# Reaccion.net
KiCad netlist of a schematic drawn in EAGLE
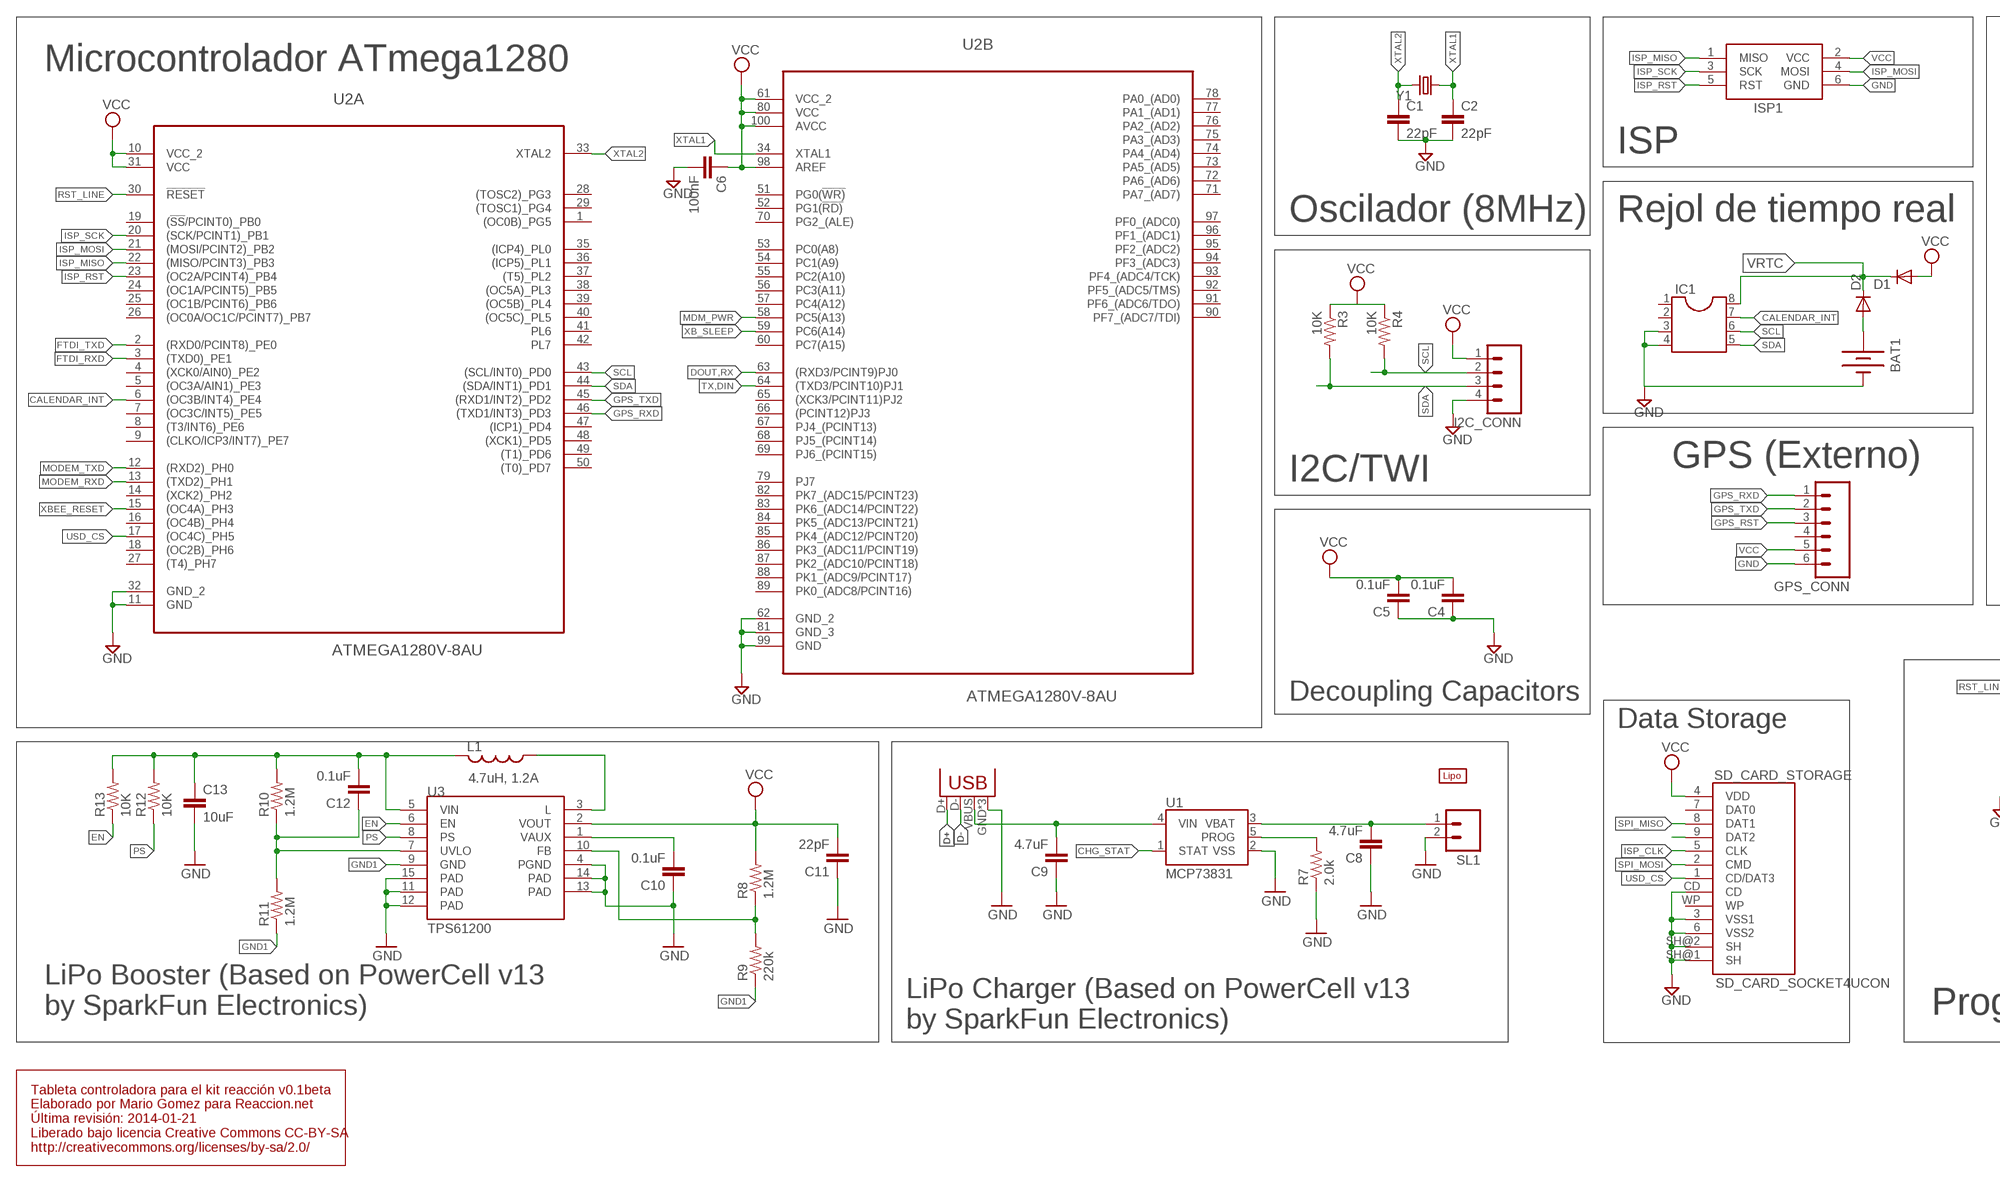
[diagram p0: schematic, sheet 1, part 1 of 2]
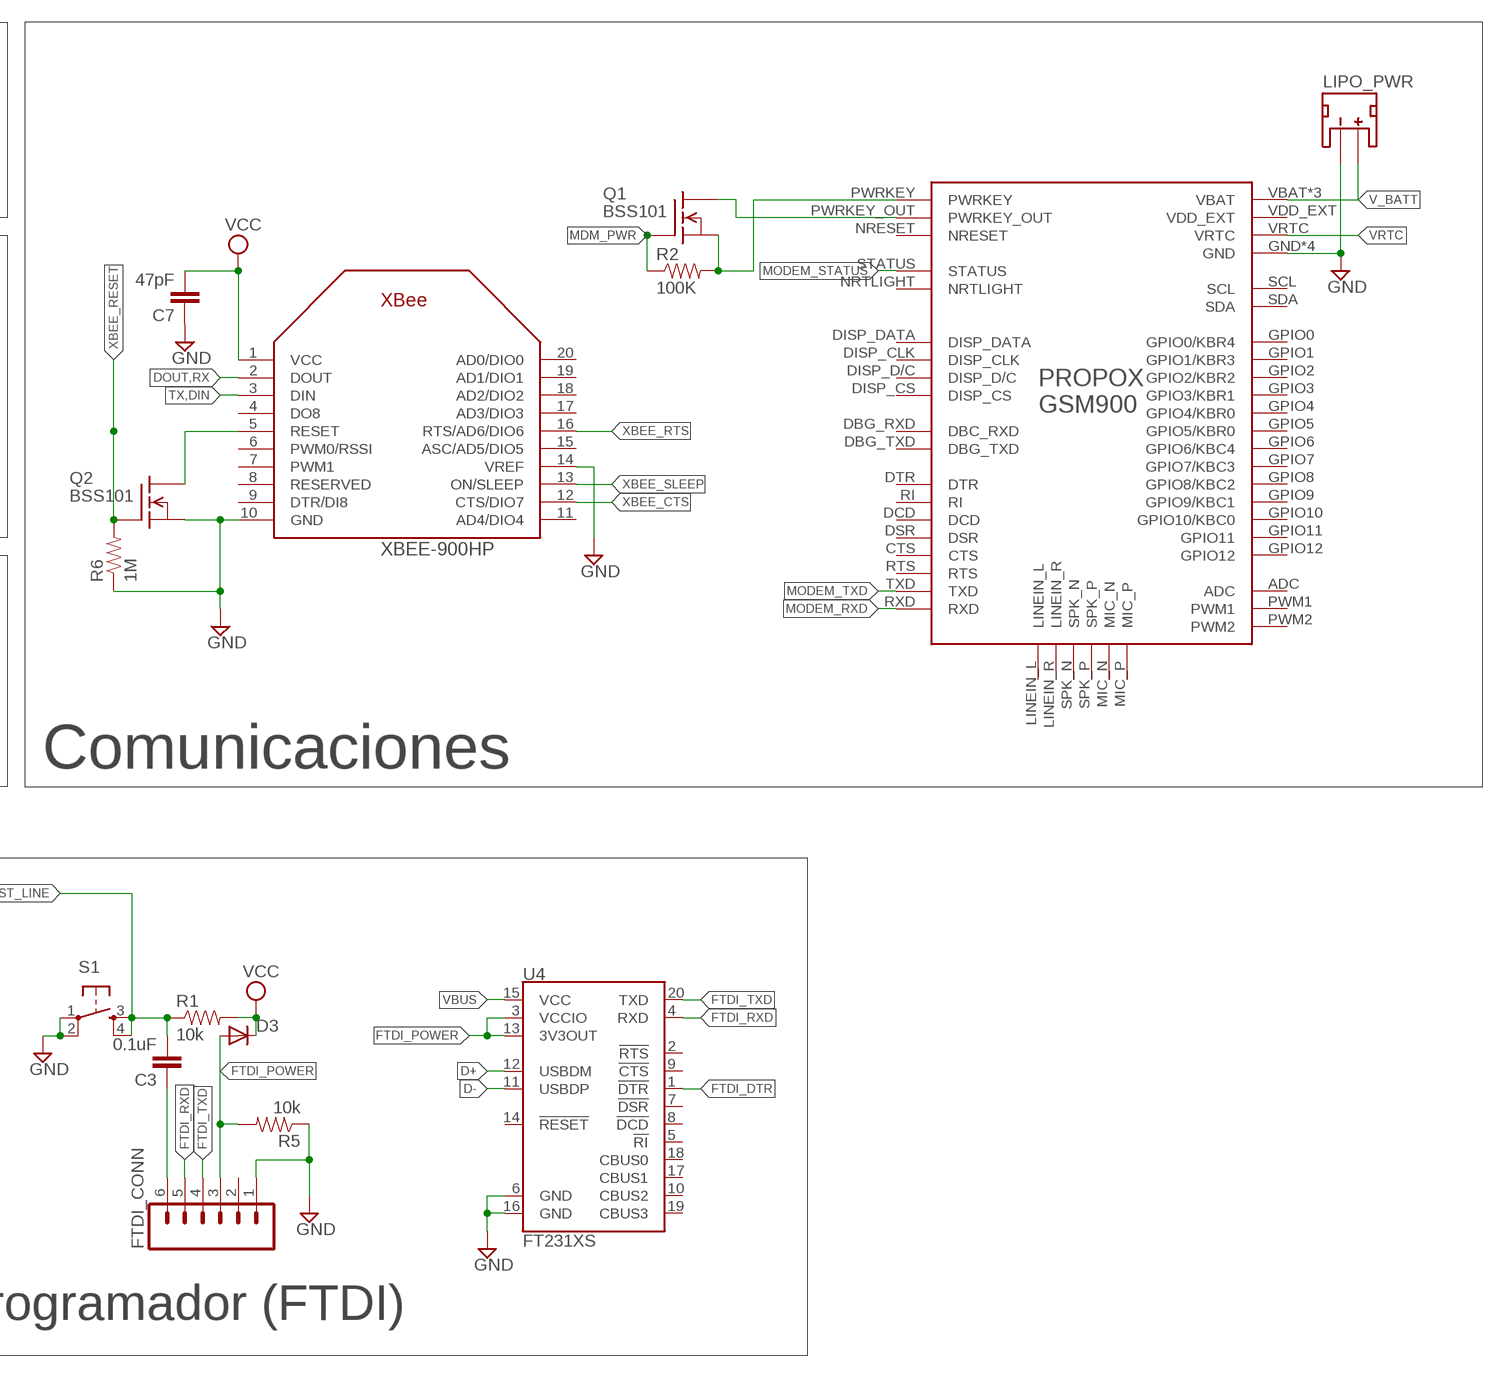
[diagram p1: schematic, sheet 1, part 2 of 2]

(export (version "E")
  (design (tool "Eeschema 10.0.6"))
  (components
    (comp (ref "BAT1")
      (value "BATTERY12PTH")
      (footprint "eagle-import:BATTCON_12MM_PTH")
      (libsource (lib "eagle-import") (part "BATTERY12PTH"))
    )
    (comp (ref "C1")
      (value "22pF")
      (footprint "eagle-import:0805")
      (libsource (lib "eagle-import") (part "CAP0805"))
    )
    (comp (ref "C2")
      (value "22pF")
      (footprint "eagle-import:0805")
      (libsource (lib "eagle-import") (part "CAP0805"))
    )
    (comp (ref "C3")
      (value "0.1uF")
      (footprint "eagle-import:0805")
      (libsource (lib "eagle-import") (part "CAP0805"))
    )
    (comp (ref "C4")
      (value "0.1uF")
      (footprint "eagle-import:0805")
      (libsource (lib "eagle-import") (part "1.0UF-25V-+80/-20(0805)"))
    )
    (comp (ref "C5")
      (value "0.1uF")
      (footprint "eagle-import:0805")
      (libsource (lib "eagle-import") (part "CAP0805"))
    )
    (comp (ref "C6")
      (value "100nF")
      (footprint "eagle-import:0805")
      (libsource (lib "eagle-import") (part "CAP0805"))
    )
    (comp (ref "C7")
      (value "47pF")
      (footprint "eagle-import:0805")
      (libsource (lib "eagle-import") (part "1.0UF-25V-+80/-20(0805)"))
    )
    (comp (ref "C8")
      (value "4.7uF")
      (footprint "eagle-import:0603-CAP")
      (libsource (lib "eagle-import") (part "4.7UF-6.3V-10%(0603)0603"))
    )
    (comp (ref "C9")
      (value "4.7uF")
      (footprint "eagle-import:0603-CAP")
      (libsource (lib "eagle-import") (part "4.7UF-6.3V-10%(0603)0603"))
    )
    (comp (ref "C10")
      (value "0.1uF")
      (footprint "eagle-import:0805")
      (libsource (lib "eagle-import") (part "1.0UF-25V-+80/-20(0805)"))
    )
    (comp (ref "C11")
      (value "22pF")
      (footprint "eagle-import:0805")
      (libsource (lib "eagle-import") (part "1.0UF-25V-+80/-20(0805)"))
    )
    (comp (ref "C12")
      (value "0.1uF")
      (footprint "eagle-import:0805")
      (libsource (lib "eagle-import") (part "1.0UF-25V-+80/-20(0805)"))
    )
    (comp (ref "C13")
      (value "10uF")
      (footprint "eagle-import:1206")
      (libsource (lib "eagle-import") (part "2.2UF-CERCAP-10009"))
    )
    (comp (ref "D1")
      (value "DIODESOD")
      (footprint "eagle-import:SOD-323")
      (libsource (lib "eagle-import") (part "DIODESOD"))
    )
    (comp (ref "D2")
      (value "DIODESOD")
      (footprint "eagle-import:SOD-323")
      (libsource (lib "eagle-import") (part "DIODESOD"))
    )
    (comp (ref "D3")
      (value "DIODESOD")
      (footprint "eagle-import:SOD-323")
      (libsource (lib "eagle-import") (part "DIODESOD"))
    )
    (comp (ref "FTDI_CONN")
      (value "M06SIP")
      (footprint "eagle-import:1X06")
      (libsource (lib "eagle-import") (part "M06SIP"))
    )
    (comp (ref "GPS_CONN")
      (value "M06SIP")
      (footprint "eagle-import:1X06")
      (libsource (lib "eagle-import") (part "M06SIP"))
    )
    (comp (ref "GSM_MODEM")
      (value "PROPOXGSM900")
      (footprint "eagle-import:CONN-13X2")
      (libsource (lib "eagle-import") (part "PROPOXGSM900"))
    )
    (comp (ref "I2C_CONN")
      (value "M04PTH")
      (footprint "eagle-import:1X04")
      (libsource (lib "eagle-import") (part "M04PTH"))
    )
    (comp (ref "IC1")
      (value "DIL8")
      (footprint "eagle-import:DIL08")
      (libsource (lib "eagle-import") (part "DIL8"))
    )
    (comp (ref "ISP1")
      (value "AVRISP-6")
      (footprint "eagle-import:AVRISP")
      (libsource (lib "eagle-import") (part "AVRISP-6"))
    )
    (comp (ref "JP1")
      (value "USB-MICROB")
      (footprint "eagle-import:USB-MICROB")
      (libsource (lib "eagle-import") (part "USB-MICROB"))
    )
    (comp (ref "L1")
      (value "4.7uH, 1.2A")
      (footprint "eagle-import:CDRH2D09")
      (libsource (lib "eagle-import") (part "INDUCTOR."))
    )
    (comp (ref "LIPO_PWR")
      (value "JST_2MM_MALE")
      (footprint "eagle-import:JST-2-SMD")
      (libsource (lib "eagle-import") (part "JST_2MM_MALE"))
    )
    (comp (ref "Q1")
      (value "BSS101")
      (footprint "eagle-import:TO92")
      (libsource (lib "eagle-import") (part "BSS101"))
    )
    (comp (ref "Q2")
      (value "BSS101")
      (footprint "eagle-import:TO92")
      (libsource (lib "eagle-import") (part "BSS101"))
    )
    (comp (ref "R1")
      (value "10k")
      (footprint "eagle-import:0805")
      (libsource (lib "eagle-import") (part "RESISTOR0805-RES"))
    )
    (comp (ref "R2")
      (value "100K")
      (footprint "eagle-import:0805")
      (libsource (lib "eagle-import") (part "RESISTOR0805-RES"))
    )
    (comp (ref "R3")
      (value "10K")
      (footprint "eagle-import:0805")
      (libsource (lib "eagle-import") (part "RESISTOR0805-RES"))
    )
    (comp (ref "R4")
      (value "10K")
      (footprint "eagle-import:0805")
      (libsource (lib "eagle-import") (part "RESISTOR0805-RES"))
    )
    (comp (ref "R5")
      (value "10k")
      (footprint "eagle-import:0805")
      (libsource (lib "eagle-import") (part "RESISTOR0805-RES"))
    )
    (comp (ref "R6")
      (value "1M")
      (footprint "eagle-import:0805")
      (libsource (lib "eagle-import") (part "RESISTOR0805-RES"))
    )
    (comp (ref "R7")
      (value "2.0k")
      (footprint "eagle-import:0603-RES")
      (libsource (lib "eagle-import") (part "2.0KOHM1/10W5%(0603)"))
    )
    (comp (ref "R8")
      (value "1.2M")
      (footprint "eagle-import:0603-RES")
      (libsource (lib "eagle-import") (part "2.0KOHM1/10W5%(0603)"))
    )
    (comp (ref "R9")
      (value "220k")
      (footprint "eagle-import:0603-RES")
      (libsource (lib "eagle-import") (part "2.0KOHM1/10W5%(0603)"))
    )
    (comp (ref "R10")
      (value "1.2M")
      (footprint "eagle-import:0603-RES")
      (libsource (lib "eagle-import") (part "2.0KOHM1/10W5%(0603)"))
    )
    (comp (ref "R11")
      (value "1.2M")
      (footprint "eagle-import:0603-RES")
      (libsource (lib "eagle-import") (part "2.0KOHM1/10W5%(0603)"))
    )
    (comp (ref "R12")
      (value "10K")
      (footprint "eagle-import:0603-RES")
      (libsource (lib "eagle-import") (part "2.0KOHM1/10W5%(0603)"))
    )
    (comp (ref "R13")
      (value "10K")
      (footprint "eagle-import:0603-RES")
      (libsource (lib "eagle-import") (part "2.0KOHM1/10W5%(0603)"))
    )
    (comp (ref "S1")
      (value "TAC_SWITCHPTH")
      (footprint "eagle-import:TACTILE-PTH")
      (libsource (lib "eagle-import") (part "TAC_SWITCHPTH"))
    )
    (comp (ref "SD_CARD_STORAGE")
      (value "SD_CARD_SOCKET4UCON")
      (footprint "eagle-import:SDCARD_4UCONN")
      (libsource (lib "eagle-import") (part "SD_CARD_SOCKET4UCON"))
    )
    (comp (ref "SL1")
      (value "M02")
      (footprint "eagle-import:02P")
      (libsource (lib "eagle-import") (part "M02"))
    )
    (comp (ref "U$2")
      (value "LIPO-OUTLINE2000")
      (footprint "eagle-import:LIPO-2000")
      (libsource (lib "eagle-import") (part "LIPO-OUTLINE2000"))
    )
    (comp (ref "U1")
      (value "MCP73831")
      (footprint "eagle-import:SOT23-5")
      (libsource (lib "eagle-import") (part "MCP73831"))
    )
    (comp (ref "U2")
      (value "ATMEGA1280V-8AU")
      (footprint "eagle-import:QFP50P1600X1600X120-100N")
      (libsource (lib "eagle-import") (part "ATMEGA1280V-8AU"))
    )
    (comp (ref "U3")
      (value "TPS61200")
      (footprint "eagle-import:QFN-10_PAD")
      (libsource (lib "eagle-import") (part "TPS61200"))
    )
    (comp (ref "U4")
      (value "FT231XS")
      (footprint "eagle-import:SSOP20_L")
      (libsource (lib "eagle-import") (part "FT231XS"))
    )
    (comp (ref "XBEE-900HP")
      (value "XBEE")
      (footprint "eagle-import:XBEE")
      (libsource (lib "eagle-import") (part "XBEE"))
    )
    (comp (ref "Y1")
      (value "CRYSTAL10.5X4.8")
      (footprint "eagle-import:CRYSTAL-SMD-10.5X4.8-2PIN")
      (libsource (lib "eagle-import") (part "CRYSTAL10.5X4.8"))
    )
  )
  (nets
    (net (code "1") (name "CALENDAR_INT") (class "Default")
      (node (ref "IC1") (pin "7") (pinfunction "7_7") (pintype "passive"))
      (node (ref "U2") (pin "6") (pinfunction "(OC3B/INT4)_PE4_6") (pintype "bidirectional"))
    )
    (net (code "2") (name "CHG_STAT") (class "Default")
      (node (ref "U1") (pin "1") (pinfunction "STAT_1") (pintype "output"))
    )
    (net (code "3") (name "D+") (class "Default")
      (node (ref "JP1") (pin "D+") (pinfunction "D+_D+") (pintype "bidirectional"))
      (node (ref "U4") (pin "12") (pinfunction "USBDM_12") (pintype "bidirectional"))
    )
    (net (code "4") (name "D-") (class "Default")
      (node (ref "JP1") (pin "D-") (pinfunction "D-_D-") (pintype "bidirectional"))
      (node (ref "U4") (pin "11") (pinfunction "USBDP_11") (pintype "bidirectional"))
    )
    (net (code "5") (name "DOUT,RX") (class "Default")
      (node (ref "U2") (pin "63") (pinfunction "(RXD3/PCINT9)PJ0_63") (pintype "bidirectional"))
      (node (ref "XBEE-900HP") (pin "2") (pinfunction "DOUT_2") (pintype "output"))
    )
    (net (code "6") (name "EN") (class "Default")
      (node (ref "R13") (pin "1") (pinfunction "1_1") (pintype "passive"))
      (node (ref "U3") (pin "6") (pinfunction "EN_6") (pintype "input"))
    )
    (net (code "7") (name "FTDI_DTR") (class "Default")
      (node (ref "C3") (pin "1") (pinfunction "1_1") (pintype "passive"))
      (node (ref "FTDI_CONN") (pin "6") (pinfunction "6_6") (pintype "passive"))
      (node (ref "U4") (pin "1") (pinfunction "~{DTR}_1") (pintype "bidirectional"))
    )
    (net (code "8") (name "FTDI_POWER") (class "Default")
      (node (ref "D3") (pin "2") (pinfunction "A_2") (pintype "passive"))
      (node (ref "FTDI_CONN") (pin "3") (pinfunction "3_3") (pintype "passive"))
      (node (ref "R5") (pin "2") (pinfunction "2_2") (pintype "passive"))
      (node (ref "U4") (pin "13") (pinfunction "3V3OUT_13") (pintype "bidirectional"))
      (node (ref "U4") (pin "3") (pinfunction "VCCIO_3") (pintype "bidirectional"))
    )
    (net (code "9") (name "FTDI_RXD") (class "Default")
      (node (ref "FTDI_CONN") (pin "5") (pinfunction "5_5") (pintype "passive"))
      (node (ref "U2") (pin "3") (pinfunction "(TXD0)_PE1_3") (pintype "bidirectional"))
      (node (ref "U4") (pin "4") (pinfunction "RXD_4") (pintype "bidirectional"))
    )
    (net (code "10") (name "FTDI_TXD") (class "Default")
      (node (ref "FTDI_CONN") (pin "4") (pinfunction "4_4") (pintype "passive"))
      (node (ref "U2") (pin "2") (pinfunction "(RXD0/PCINT8)_PE0_2") (pintype "bidirectional"))
      (node (ref "U4") (pin "20") (pinfunction "TXD_20") (pintype "bidirectional"))
    )
    (net (code "11") (name "GND") (class "Default")
      (node (ref "BAT1") (pin "GND") (pinfunction "-_GND") (pintype "power_in"))
      (node (ref "C1") (pin "2") (pinfunction "2_2") (pintype "passive"))
      (node (ref "C10") (pin "1") (pinfunction "1_1") (pintype "passive"))
      (node (ref "C11") (pin "1") (pinfunction "1_1") (pintype "passive"))
      (node (ref "C13") (pin "2") (pinfunction "2_2") (pintype "passive"))
      (node (ref "C2") (pin "2") (pinfunction "2_2") (pintype "passive"))
      (node (ref "C4") (pin "1") (pinfunction "1_1") (pintype "passive"))
      (node (ref "C5") (pin "1") (pinfunction "1_1") (pintype "passive"))
      (node (ref "C6") (pin "2") (pinfunction "2_2") (pintype "passive"))
      (node (ref "C7") (pin "1") (pinfunction "1_1") (pintype "passive"))
      (node (ref "C8") (pin "1") (pinfunction "1_1") (pintype "passive"))
      (node (ref "C9") (pin "1") (pinfunction "1_1") (pintype "passive"))
      (node (ref "FTDI_CONN") (pin "1") (pinfunction "1_1") (pintype "passive"))
      (node (ref "GPS_CONN") (pin "6") (pinfunction "6_6") (pintype "passive"))
      (node (ref "GSM_MODEM") (pin "GND") (pinfunction "GND_GND") (pintype "power_in"))
      (node (ref "GSM_MODEM") (pin "GND2") (pinfunction "GND_GND2") (pintype "power_in"))
      (node (ref "GSM_MODEM") (pin "GND3") (pinfunction "GND_GND3") (pintype "power_in"))
      (node (ref "GSM_MODEM") (pin "GND4") (pinfunction "GND_GND4") (pintype "power_in"))
      (node (ref "I2C_CONN") (pin "4") (pinfunction "4_4") (pintype "passive"))
      (node (ref "IC1") (pin "3") (pinfunction "3_3") (pintype "passive"))
      (node (ref "IC1") (pin "4") (pinfunction "4_4") (pintype "passive"))
      (node (ref "ISP1") (pin "6") (pinfunction "GND_6") (pintype "power_in"))
      (node (ref "JP1") (pin "GND") (pinfunction "GND_GND") (pintype "bidirectional"))
      (node (ref "JP1") (pin "MT1") (pinfunction "GND_MT1") (pintype "bidirectional"))
      (node (ref "JP1") (pin "MT2") (pinfunction "GND_MT2") (pintype "bidirectional"))
      (node (ref "LIPO_PWR") (pin "1") (pinfunction "-_1") (pintype "bidirectional"))
      (node (ref "Q2") (pin "1") (pinfunction "S_1") (pintype "passive"))
      (node (ref "R5") (pin "1") (pinfunction "1_1") (pintype "passive"))
      (node (ref "R6") (pin "1") (pinfunction "1_1") (pintype "passive"))
      (node (ref "R7") (pin "1") (pinfunction "1_1") (pintype "passive"))
      (node (ref "S1") (pin "1") (pinfunction "1_1") (pintype "passive"))
      (node (ref "S1") (pin "2") (pinfunction "2_2") (pintype "passive"))
      (node (ref "SD_CARD_STORAGE") (pin "3") (pinfunction "VSS1_3") (pintype "power_in"))
      (node (ref "SD_CARD_STORAGE") (pin "6") (pinfunction "VSS2_6") (pintype "power_in"))
      (node (ref "SD_CARD_STORAGE") (pin "CD") (pinfunction "CD_CD") (pintype "bidirectional"))
      (node (ref "SD_CARD_STORAGE") (pin "SH@1") (pinfunction "SH_SH@1") (pintype "bidirectional"))
      (node (ref "SD_CARD_STORAGE") (pin "SH@2") (pinfunction "SH_SH@2") (pintype "bidirectional"))
      (node (ref "SL1") (pin "2") (pinfunction "2_2") (pintype "passive"))
      (node (ref "U1") (pin "2") (pinfunction "VSS_2") (pintype "power_in"))
      (node (ref "U2") (pin "11") (pinfunction "GND_11") (pintype "passive"))
      (node (ref "U2") (pin "32") (pinfunction "GND_2_32") (pintype "passive"))
      (node (ref "U2") (pin "62") (pinfunction "GND_2_62") (pintype "passive"))
      (node (ref "U2") (pin "81") (pinfunction "GND_3_81") (pintype "passive"))
      (node (ref "U2") (pin "99") (pinfunction "GND_99") (pintype "passive"))
      (node (ref "U3") (pin "11") (pinfunction "PAD_11") (pintype "power_in"))
      (node (ref "U3") (pin "12") (pinfunction "PAD_12") (pintype "power_in"))
      (node (ref "U3") (pin "13") (pinfunction "PAD_13") (pintype "power_in"))
      (node (ref "U3") (pin "14") (pinfunction "PAD_14") (pintype "power_in"))
      (node (ref "U3") (pin "15") (pinfunction "PAD_15") (pintype "power_in"))
      (node (ref "U3") (pin "4") (pinfunction "PGND_4") (pintype "power_in"))
      (node (ref "U4") (pin "16") (pinfunction "GND_16") (pintype "bidirectional"))
      (node (ref "U4") (pin "6") (pinfunction "GND_6") (pintype "bidirectional"))
      (node (ref "XBEE-900HP") (pin "10") (pinfunction "GND_10") (pintype "power_in"))
      (node (ref "XBEE-900HP") (pin "14") (pinfunction "VREF_14") (pintype "input"))
    )
    (net (code "12") (name "GND1") (class "Default")
      (node (ref "R11") (pin "1") (pinfunction "1_1") (pintype "passive"))
      (node (ref "R9") (pin "1") (pinfunction "1_1") (pintype "passive"))
      (node (ref "U3") (pin "9") (pinfunction "GND_9") (pintype "power_in"))
    )
    (net (code "13") (name "GPS_RST") (class "Default")
      (node (ref "GPS_CONN") (pin "3") (pinfunction "3_3") (pintype "passive"))
    )
    (net (code "14") (name "GPS_RXD") (class "Default")
      (node (ref "GPS_CONN") (pin "1") (pinfunction "1_1") (pintype "passive"))
      (node (ref "U2") (pin "46") (pinfunction "(TXD1/INT3)_PD3_46") (pintype "bidirectional"))
    )
    (net (code "15") (name "GPS_TXD") (class "Default")
      (node (ref "GPS_CONN") (pin "2") (pinfunction "2_2") (pintype "passive"))
      (node (ref "U2") (pin "45") (pinfunction "(RXD1/INT2)_PD2_45") (pintype "bidirectional"))
    )
    (net (code "16") (name "ISP_CLK") (class "Default")
      (node (ref "SD_CARD_STORAGE") (pin "5") (pinfunction "CLK_5") (pintype "bidirectional"))
    )
    (net (code "17") (name "ISP_MISO") (class "Default")
      (node (ref "ISP1") (pin "1") (pinfunction "MISO_1") (pintype "input"))
      (node (ref "U2") (pin "22") (pinfunction "(MISO/PCINT3)_PB3_22") (pintype "bidirectional"))
    )
    (net (code "18") (name "ISP_MOSI") (class "Default")
      (node (ref "ISP1") (pin "4") (pinfunction "MOSI_4") (pintype "output"))
      (node (ref "U2") (pin "21") (pinfunction "(MOSI/PCINT2)_PB2_21") (pintype "bidirectional"))
    )
    (net (code "19") (name "ISP_RST") (class "Default")
      (node (ref "ISP1") (pin "5") (pinfunction "RST_5") (pintype "output"))
      (node (ref "U2") (pin "23") (pinfunction "(OC2A/PCINT4)_PB4_23") (pintype "bidirectional"))
    )
    (net (code "20") (name "ISP_SCK") (class "Default")
      (node (ref "ISP1") (pin "3") (pinfunction "SCK_3") (pintype "output"))
      (node (ref "U2") (pin "20") (pinfunction "(SCK/PCINT1)_PB1_20") (pintype "bidirectional"))
    )
    (net (code "21") (name "MDM_PWR") (class "Default")
      (node (ref "Q1") (pin "2") (pinfunction "G_2") (pintype "passive"))
      (node (ref "R2") (pin "1") (pinfunction "1_1") (pintype "passive"))
      (node (ref "U2") (pin "58") (pinfunction "PC5(A13)_58") (pintype "bidirectional"))
    )
    (net (code "22") (name "MODEM_RXD") (class "Default")
      (node (ref "GSM_MODEM") (pin "RXD") (pinfunction "RXD_RXD") (pintype "bidirectional"))
      (node (ref "U2") (pin "13") (pinfunction "(TXD2)_PH1_13") (pintype "bidirectional"))
    )
    (net (code "23") (name "MODEM_STATUS") (class "Default")
      (node (ref "GSM_MODEM") (pin "STATUS") (pinfunction "STATUS_STATUS") (pintype "bidirectional"))
    )
    (net (code "24") (name "MODEM_TXD") (class "Default")
      (node (ref "GSM_MODEM") (pin "TXD") (pinfunction "TXD_TXD") (pintype "bidirectional"))
      (node (ref "U2") (pin "12") (pinfunction "(RXD2)_PH0_12") (pintype "bidirectional"))
    )
    (net (code "25") (name "Net-(BAT1-+)") (class "Default")
      (node (ref "BAT1") (pin "VCC@1") (pinfunction "+_VCC@1") (pintype "power_in"))
      (node (ref "D2") (pin "2") (pinfunction "A_2") (pintype "passive"))
    )
    (net (code "26") (name "Net-(L1-1)") (class "Default")
      (node (ref "L1") (pin "P$1") (pinfunction "1_P$1") (pintype "passive"))
      (node (ref "U3") (pin "3") (pinfunction "L_3") (pintype "passive"))
    )
    (net (code "27") (name "Net-(Q1-D)") (class "Default")
      (node (ref "GSM_MODEM") (pin "PWRKEY_OUT") (pinfunction "PWRKEY_OUT_PWRKEY_OUT") (pintype "bidirectional"))
      (node (ref "Q1") (pin "3") (pinfunction "D_3") (pintype "passive"))
    )
    (net (code "28") (name "Net-(Q1-S)") (class "Default")
      (node (ref "GSM_MODEM") (pin "PWRKEY") (pinfunction "PWRKEY_PWRKEY") (pintype "bidirectional"))
      (node (ref "Q1") (pin "1") (pinfunction "S_1") (pintype "passive"))
      (node (ref "R2") (pin "2") (pinfunction "2_2") (pintype "passive"))
    )
    (net (code "29") (name "Net-(Q2-D)") (class "Default")
      (node (ref "Q2") (pin "3") (pinfunction "D_3") (pintype "passive"))
      (node (ref "XBEE-900HP") (pin "5") (pinfunction "RESET_5") (pintype "input"))
    )
    (net (code "30") (name "Net-(U1-PROG)") (class "Default")
      (node (ref "R7") (pin "2") (pinfunction "2_2") (pintype "passive"))
      (node (ref "U1") (pin "5") (pinfunction "PROG_5") (pintype "input"))
    )
    (net (code "31") (name "Net-(U3-FB)") (class "Default")
      (node (ref "R8") (pin "1") (pinfunction "1_1") (pintype "passive"))
      (node (ref "R9") (pin "2") (pinfunction "2_2") (pintype "passive"))
      (node (ref "U3") (pin "10") (pinfunction "FB_10") (pintype "passive"))
    )
    (net (code "32") (name "Net-(U3-UVLO)") (class "Default")
      (node (ref "C12") (pin "1") (pinfunction "1_1") (pintype "passive"))
      (node (ref "R10") (pin "1") (pinfunction "1_1") (pintype "passive"))
      (node (ref "R11") (pin "2") (pinfunction "2_2") (pintype "passive"))
      (node (ref "U3") (pin "7") (pinfunction "UVLO_7") (pintype "passive"))
    )
    (net (code "33") (name "Net-(U3-VAUX)") (class "Default")
      (node (ref "C10") (pin "2") (pinfunction "2_2") (pintype "passive"))
      (node (ref "U3") (pin "1") (pinfunction "VAUX_1") (pintype "passive"))
    )
    (net (code "34") (name "PS") (class "Default")
      (node (ref "R12") (pin "1") (pinfunction "1_1") (pintype "passive"))
      (node (ref "U3") (pin "8") (pinfunction "PS_8") (pintype "input"))
    )
    (net (code "35") (name "RST_LINE") (class "Default")
      (node (ref "C3") (pin "2") (pinfunction "2_2") (pintype "passive"))
      (node (ref "R1") (pin "1") (pinfunction "1_1") (pintype "passive"))
      (node (ref "S1") (pin "3") (pinfunction "3_3") (pintype "passive"))
      (node (ref "S1") (pin "4") (pinfunction "4_4") (pintype "passive"))
      (node (ref "U2") (pin "30") (pinfunction "~{RESET}_30") (pintype "input"))
    )
    (net (code "36") (name "SCL") (class "Default")
      (node (ref "I2C_CONN") (pin "2") (pinfunction "2_2") (pintype "passive"))
      (node (ref "IC1") (pin "6") (pinfunction "6_6") (pintype "passive"))
      (node (ref "R4") (pin "2") (pinfunction "2_2") (pintype "passive"))
      (node (ref "U2") (pin "43") (pinfunction "(SCL/INT0)_PD0_43") (pintype "bidirectional"))
    )
    (net (code "37") (name "SDA") (class "Default")
      (node (ref "I2C_CONN") (pin "3") (pinfunction "3_3") (pintype "passive"))
      (node (ref "IC1") (pin "5") (pinfunction "5_5") (pintype "passive"))
      (node (ref "R3") (pin "2") (pinfunction "2_2") (pintype "passive"))
      (node (ref "U2") (pin "44") (pinfunction "(SDA/INT1)_PD1_44") (pintype "bidirectional"))
    )
    (net (code "38") (name "SPI_MISO") (class "Default")
      (node (ref "SD_CARD_STORAGE") (pin "8") (pinfunction "DAT1_8") (pintype "bidirectional"))
    )
    (net (code "39") (name "SPI_MOSI") (class "Default")
      (node (ref "SD_CARD_STORAGE") (pin "2") (pinfunction "CMD_2") (pintype "bidirectional"))
    )
    (net (code "40") (name "TX,DIN") (class "Default")
      (node (ref "U2") (pin "64") (pinfunction "(TXD3/PCINT10)PJ1_64") (pintype "bidirectional"))
      (node (ref "XBEE-900HP") (pin "3") (pinfunction "DIN_3") (pintype "input"))
    )
    (net (code "41") (name "USD_CS") (class "Default")
      (node (ref "SD_CARD_STORAGE") (pin "1") (pinfunction "CD/DAT3_1") (pintype "bidirectional"))
      (node (ref "U2") (pin "17") (pinfunction "(OC4C)_PH5_17") (pintype "bidirectional"))
    )
    (net (code "42") (name "VBUS") (class "Default")
      (node (ref "C9") (pin "2") (pinfunction "2_2") (pintype "passive"))
      (node (ref "JP1") (pin "VBUS") (pinfunction "VBUS_VBUS") (pintype "bidirectional"))
      (node (ref "U1") (pin "4") (pinfunction "VIN_4") (pintype "power_in"))
      (node (ref "U4") (pin "15") (pinfunction "VCC_15") (pintype "bidirectional"))
    )
    (net (code "43") (name "VCC") (class "Default")
      (node (ref "C11") (pin "2") (pinfunction "2_2") (pintype "passive"))
      (node (ref "C4") (pin "2") (pinfunction "2_2") (pintype "passive"))
      (node (ref "C5") (pin "2") (pinfunction "2_2") (pintype "passive"))
      (node (ref "C6") (pin "1") (pinfunction "1_1") (pintype "passive"))
      (node (ref "C7") (pin "2") (pinfunction "2_2") (pintype "passive"))
      (node (ref "D1") (pin "2") (pinfunction "A_2") (pintype "passive"))
      (node (ref "D3") (pin "1") (pinfunction "C_1") (pintype "passive"))
      (node (ref "GPS_CONN") (pin "5") (pinfunction "5_5") (pintype "passive"))
      (node (ref "I2C_CONN") (pin "1") (pinfunction "1_1") (pintype "passive"))
      (node (ref "ISP1") (pin "2") (pinfunction "VCC_2") (pintype "power_in"))
      (node (ref "R1") (pin "2") (pinfunction "2_2") (pintype "passive"))
      (node (ref "R3") (pin "1") (pinfunction "1_1") (pintype "passive"))
      (node (ref "R4") (pin "1") (pinfunction "1_1") (pintype "passive"))
      (node (ref "R8") (pin "2") (pinfunction "2_2") (pintype "passive"))
      (node (ref "SD_CARD_STORAGE") (pin "4") (pinfunction "VDD_4") (pintype "power_in"))
      (node (ref "U2") (pin "10") (pinfunction "VCC_2_10") (pintype "power_in"))
      (node (ref "U2") (pin "100") (pinfunction "AVCC_100") (pintype "power_in"))
      (node (ref "U2") (pin "31") (pinfunction "VCC_31") (pintype "power_in"))
      (node (ref "U2") (pin "61") (pinfunction "VCC_2_61") (pintype "power_in"))
      (node (ref "U2") (pin "80") (pinfunction "VCC_80") (pintype "power_in"))
      (node (ref "U2") (pin "98") (pinfunction "AREF_98") (pintype "passive"))
      (node (ref "U3") (pin "2") (pinfunction "VOUT_2") (pintype "passive"))
      (node (ref "XBEE-900HP") (pin "1") (pinfunction "VCC_1") (pintype "power_in"))
    )
    (net (code "44") (name "VRTC") (class "Default")
      (node (ref "D1") (pin "1") (pinfunction "C_1") (pintype "passive"))
      (node (ref "D2") (pin "1") (pinfunction "C_1") (pintype "passive"))
      (node (ref "GSM_MODEM") (pin "VRTC") (pinfunction "VRTC_VRTC") (pintype "bidirectional"))
      (node (ref "IC1") (pin "8") (pinfunction "8_8") (pintype "passive"))
    )
    (net (code "45") (name "V_BATT") (class "Default")
      (node (ref "C12") (pin "2") (pinfunction "2_2") (pintype "passive"))
      (node (ref "C13") (pin "1") (pinfunction "1_1") (pintype "passive"))
      (node (ref "C8") (pin "2") (pinfunction "2_2") (pintype "passive"))
      (node (ref "GSM_MODEM") (pin "VBAT") (pinfunction "VBAT_VBAT") (pintype "power_in"))
      (node (ref "GSM_MODEM") (pin "VBAT2") (pinfunction "VBAT_VBAT2") (pintype "power_in"))
      (node (ref "GSM_MODEM") (pin "VBAT3") (pinfunction "VBAT_VBAT3") (pintype "power_in"))
      (node (ref "L1") (pin "P$2") (pinfunction "2_P$2") (pintype "passive"))
      (node (ref "LIPO_PWR") (pin "2") (pinfunction "+_2") (pintype "bidirectional"))
      (node (ref "R10") (pin "2") (pinfunction "2_2") (pintype "passive"))
      (node (ref "R12") (pin "2") (pinfunction "2_2") (pintype "passive"))
      (node (ref "R13") (pin "2") (pinfunction "2_2") (pintype "passive"))
      (node (ref "SL1") (pin "1") (pinfunction "1_1") (pintype "passive"))
      (node (ref "U1") (pin "3") (pinfunction "VBAT_3") (pintype "power_in"))
      (node (ref "U3") (pin "5") (pinfunction "VIN_5") (pintype "power_in"))
    )
    (net (code "46") (name "XBEE_CTS") (class "Default")
      (node (ref "XBEE-900HP") (pin "12") (pinfunction "CTS/DIO7_12") (pintype "bidirectional"))
    )
    (net (code "47") (name "XBEE_RESET") (class "Default")
      (node (ref "Q2") (pin "2") (pinfunction "G_2") (pintype "passive"))
      (node (ref "R6") (pin "2") (pinfunction "2_2") (pintype "passive"))
      (node (ref "U2") (pin "15") (pinfunction "(OC4A)_PH3_15") (pintype "bidirectional"))
    )
    (net (code "48") (name "XBEE_RTS") (class "Default")
      (node (ref "XBEE-900HP") (pin "16") (pinfunction "RTS/AD6/DIO6_16") (pintype "bidirectional"))
    )
    (net (code "49") (name "XBEE_SLEEP") (class "Default")
      (node (ref "XBEE-900HP") (pin "13") (pinfunction "ON/SLEEP_13") (pintype "output"))
    )
    (net (code "50") (name "XB_SLEEP") (class "Default")
      (node (ref "U2") (pin "59") (pinfunction "PC6(A14)_59") (pintype "bidirectional"))
    )
    (net (code "51") (name "XTAL1") (class "Default")
      (node (ref "C2") (pin "1") (pinfunction "1_1") (pintype "passive"))
      (node (ref "U2") (pin "34") (pinfunction "XTAL1_34") (pintype "passive"))
      (node (ref "Y1") (pin "P$1") (pinfunction "1_P$1") (pintype "passive"))
    )
    (net (code "52") (name "XTAL2") (class "Default")
      (node (ref "C1") (pin "1") (pinfunction "1_1") (pintype "passive"))
      (node (ref "U2") (pin "33") (pinfunction "XTAL2_33") (pintype "passive"))
      (node (ref "Y1") (pin "P$2") (pinfunction "2_P$2") (pintype "passive"))
    )
    (net (code "53") (name "unconnected-(FTDI_CONN-Pad2)") (class "Default")
      (node (ref "FTDI_CONN") (pin "2") (pinfunction "2_2") (pintype "passive"))
    )
    (net (code "54") (name "unconnected-(GPS_CONN-Pad4)") (class "Default")
      (node (ref "GPS_CONN") (pin "4") (pinfunction "4_4") (pintype "passive"))
    )
    (net (code "55") (name "unconnected-(GSM_MODEM-DBC_RXD-PadDBG_RXD)") (class "Default")
      (node (ref "GSM_MODEM") (pin "DBG_RXD") (pinfunction "DBC_RXD_DBG_RXD") (pintype "bidirectional"))
    )
    (net (code "56") (name "unconnected-(GSM_MODEM-GPIO0{slash}KBR4-PadGPIO0)") (class "Default")
      (node (ref "GSM_MODEM") (pin "GPIO0") (pinfunction "GPIO0/KBR4_GPIO0") (pintype "bidirectional"))
    )
    (net (code "57") (name "unconnected-(GSM_MODEM-GPIO1{slash}KBR3-PadGPIO1)") (class "Default")
      (node (ref "GSM_MODEM") (pin "GPIO1") (pinfunction "GPIO1/KBR3_GPIO1") (pintype "bidirectional"))
    )
    (net (code "58") (name "unconnected-(GSM_MODEM-GPIO2{slash}KBR2-PadGPIO2)") (class "Default")
      (node (ref "GSM_MODEM") (pin "GPIO2") (pinfunction "GPIO2/KBR2_GPIO2") (pintype "bidirectional"))
    )
    (net (code "59") (name "unconnected-(GSM_MODEM-GPIO3{slash}KBR1-PadGPIO3)") (class "Default")
      (node (ref "GSM_MODEM") (pin "GPIO3") (pinfunction "GPIO3/KBR1_GPIO3") (pintype "bidirectional"))
    )
    (net (code "60") (name "unconnected-(GSM_MODEM-GPIO4{slash}KBR0-PadGPIO4)") (class "Default")
      (node (ref "GSM_MODEM") (pin "GPIO4") (pinfunction "GPIO4/KBR0_GPIO4") (pintype "bidirectional"))
    )
    (net (code "61") (name "unconnected-(GSM_MODEM-GPIO5{slash}KBR0-PadGPIO5)") (class "Default")
      (node (ref "GSM_MODEM") (pin "GPIO5") (pinfunction "GPIO5/KBR0_GPIO5") (pintype "bidirectional"))
    )
    (net (code "62") (name "unconnected-(GSM_MODEM-GPIO6{slash}KBC4-PadGPIO6)") (class "Default")
      (node (ref "GSM_MODEM") (pin "GPIO6") (pinfunction "GPIO6/KBC4_GPIO6") (pintype "bidirectional"))
    )
    (net (code "63") (name "unconnected-(GSM_MODEM-GPIO7{slash}KBC3-PadGPIO7)") (class "Default")
      (node (ref "GSM_MODEM") (pin "GPIO7") (pinfunction "GPIO7/KBC3_GPIO7") (pintype "bidirectional"))
    )
    (net (code "64") (name "unconnected-(GSM_MODEM-GPIO8{slash}KBC2-PadGPIO8)") (class "Default")
      (node (ref "GSM_MODEM") (pin "GPIO8") (pinfunction "GPIO8/KBC2_GPIO8") (pintype "bidirectional"))
    )
    (net (code "65") (name "unconnected-(GSM_MODEM-GPIO9{slash}KBC1-PadGPIO9)") (class "Default")
      (node (ref "GSM_MODEM") (pin "GPIO9") (pinfunction "GPIO9/KBC1_GPIO9") (pintype "bidirectional"))
    )
    (net (code "66") (name "unconnected-(GSM_MODEM-GPIO10{slash}KBC0-PadGPIO10)") (class "Default")
      (node (ref "GSM_MODEM") (pin "GPIO10") (pinfunction "GPIO10/KBC0_GPIO10") (pintype "bidirectional"))
    )
    (net (code "67") (name "unconnected-(GSM_MODEM-PadADC)") (class "Default")
      (node (ref "GSM_MODEM") (pin "ADC") (pinfunction "ADC_ADC") (pintype "bidirectional"))
    )
    (net (code "68") (name "unconnected-(GSM_MODEM-PadCTS)") (class "Default")
      (node (ref "GSM_MODEM") (pin "CTS") (pinfunction "CTS_CTS") (pintype "bidirectional"))
    )
    (net (code "69") (name "unconnected-(GSM_MODEM-PadDBG_TXD)") (class "Default")
      (node (ref "GSM_MODEM") (pin "DBG_TXD") (pinfunction "DBG_TXD_DBG_TXD") (pintype "bidirectional"))
    )
    (net (code "70") (name "unconnected-(GSM_MODEM-PadDCD)") (class "Default")
      (node (ref "GSM_MODEM") (pin "DCD") (pinfunction "DCD_DCD") (pintype "bidirectional"))
    )
    (net (code "71") (name "unconnected-(GSM_MODEM-PadDISP_CLK)") (class "Default")
      (node (ref "GSM_MODEM") (pin "DISP_CLK") (pinfunction "DISP_CLK_DISP_CLK") (pintype "bidirectional"))
    )
    (net (code "72") (name "unconnected-(GSM_MODEM-PadDISP_CS)") (class "Default")
      (node (ref "GSM_MODEM") (pin "DISP_CS") (pinfunction "DISP_CS_DISP_CS") (pintype "bidirectional"))
    )
    (net (code "73") (name "unconnected-(GSM_MODEM-PadDISP_DATA)") (class "Default")
      (node (ref "GSM_MODEM") (pin "DISP_DATA") (pinfunction "DISP_DATA_DISP_DATA") (pintype "bidirectional"))
    )
    (net (code "74") (name "unconnected-(GSM_MODEM-PadDISP_D{slash}C)") (class "Default")
      (node (ref "GSM_MODEM") (pin "DISP_D/C") (pinfunction "DISP_D/C_DISP_D/C") (pintype "bidirectional"))
    )
    (net (code "75") (name "unconnected-(GSM_MODEM-PadDSR)") (class "Default")
      (node (ref "GSM_MODEM") (pin "DSR") (pinfunction "DSR_DSR") (pintype "bidirectional"))
    )
    (net (code "76") (name "unconnected-(GSM_MODEM-PadDTR)") (class "Default")
      (node (ref "GSM_MODEM") (pin "DTR") (pinfunction "DTR_DTR") (pintype "bidirectional"))
    )
    (net (code "77") (name "unconnected-(GSM_MODEM-PadGPIO11)") (class "Default")
      (node (ref "GSM_MODEM") (pin "GPIO11") (pinfunction "GPIO11_GPIO11") (pintype "bidirectional"))
    )
    (net (code "78") (name "unconnected-(GSM_MODEM-PadGPIO12)") (class "Default")
      (node (ref "GSM_MODEM") (pin "GPIO12") (pinfunction "GPIO12_GPIO12") (pintype "bidirectional"))
    )
    (net (code "79") (name "unconnected-(GSM_MODEM-PadLINEIN_L)") (class "Default")
      (node (ref "GSM_MODEM") (pin "LINEIN_L") (pinfunction "LINEIN_L_LINEIN_L") (pintype "bidirectional"))
    )
    (net (code "80") (name "unconnected-(GSM_MODEM-PadLINEIN_R)") (class "Default")
      (node (ref "GSM_MODEM") (pin "LINEIN_R") (pinfunction "LINEIN_R_LINEIN_R") (pintype "bidirectional"))
    )
    (net (code "81") (name "unconnected-(GSM_MODEM-PadMIC_N)") (class "Default")
      (node (ref "GSM_MODEM") (pin "MIC_N") (pinfunction "MIC_N_MIC_N") (pintype "bidirectional"))
    )
    (net (code "82") (name "unconnected-(GSM_MODEM-PadMIC_P)") (class "Default")
      (node (ref "GSM_MODEM") (pin "MIC_P") (pinfunction "MIC_P_MIC_P") (pintype "bidirectional"))
    )
    (net (code "83") (name "unconnected-(GSM_MODEM-PadNRESET)") (class "Default")
      (node (ref "GSM_MODEM") (pin "NRESET") (pinfunction "NRESET_NRESET") (pintype "bidirectional"))
    )
    (net (code "84") (name "unconnected-(GSM_MODEM-PadNRTLIGHT)") (class "Default")
      (node (ref "GSM_MODEM") (pin "NRTLIGHT") (pinfunction "NRTLIGHT_NRTLIGHT") (pintype "bidirectional"))
    )
    (net (code "85") (name "unconnected-(GSM_MODEM-PadPWM1)") (class "Default")
      (node (ref "GSM_MODEM") (pin "PWM1") (pinfunction "PWM1_PWM1") (pintype "bidirectional"))
    )
    (net (code "86") (name "unconnected-(GSM_MODEM-PadPWM2)") (class "Default")
      (node (ref "GSM_MODEM") (pin "PWM2") (pinfunction "PWM2_PWM2") (pintype "bidirectional"))
    )
    (net (code "87") (name "unconnected-(GSM_MODEM-PadRI)") (class "Default")
      (node (ref "GSM_MODEM") (pin "RI") (pinfunction "RI_RI") (pintype "bidirectional"))
    )
    (net (code "88") (name "unconnected-(GSM_MODEM-PadRTS)") (class "Default")
      (node (ref "GSM_MODEM") (pin "RTS") (pinfunction "RTS_RTS") (pintype "bidirectional"))
    )
    (net (code "89") (name "unconnected-(GSM_MODEM-PadSCL)") (class "Default")
      (node (ref "GSM_MODEM") (pin "SCL") (pinfunction "SCL_SCL") (pintype "bidirectional"))
    )
    (net (code "90") (name "unconnected-(GSM_MODEM-PadSDA)") (class "Default")
      (node (ref "GSM_MODEM") (pin "SDA") (pinfunction "SDA_SDA") (pintype "bidirectional"))
    )
    (net (code "91") (name "unconnected-(GSM_MODEM-PadSPK_N)") (class "Default")
      (node (ref "GSM_MODEM") (pin "SPK_N") (pinfunction "SPK_N_SPK_N") (pintype "bidirectional"))
    )
    (net (code "92") (name "unconnected-(GSM_MODEM-PadSPK_P)") (class "Default")
      (node (ref "GSM_MODEM") (pin "SPK_P") (pinfunction "SPK_P_SPK_P") (pintype "bidirectional"))
    )
    (net (code "93") (name "unconnected-(GSM_MODEM-PadVDD_EXT)") (class "Default")
      (node (ref "GSM_MODEM") (pin "VDD_EXT") (pinfunction "VDD_EXT_VDD_EXT") (pintype "output"))
    )
    (net (code "94") (name "unconnected-(IC1-Pad1)") (class "Default")
      (node (ref "IC1") (pin "1") (pinfunction "1_1") (pintype "passive"))
    )
    (net (code "95") (name "unconnected-(IC1-Pad2)") (class "Default")
      (node (ref "IC1") (pin "2") (pinfunction "2_2") (pintype "passive"))
    )
    (net (code "96") (name "unconnected-(LIPO_PWR-PAD1-PadNC1)") (class "Default")
      (node (ref "LIPO_PWR") (pin "NC1") (pinfunction "PAD1_NC1") (pintype "bidirectional"))
    )
    (net (code "97") (name "unconnected-(LIPO_PWR-PAD2-PadNC2)") (class "Default")
      (node (ref "LIPO_PWR") (pin "NC2") (pinfunction "PAD2_NC2") (pintype "bidirectional"))
    )
    (net (code "98") (name "unconnected-(SD_CARD_STORAGE-DAT0-Pad7)") (class "Default")
      (node (ref "SD_CARD_STORAGE") (pin "7") (pinfunction "DAT0_7") (pintype "bidirectional"))
    )
    (net (code "99") (name "unconnected-(SD_CARD_STORAGE-DAT2-Pad9)") (class "Default")
      (node (ref "SD_CARD_STORAGE") (pin "9") (pinfunction "DAT2_9") (pintype "bidirectional"))
    )
    (net (code "100") (name "unconnected-(SD_CARD_STORAGE-PadWP)") (class "Default")
      (node (ref "SD_CARD_STORAGE") (pin "WP") (pinfunction "WP_WP") (pintype "bidirectional"))
    )
    (net (code "101") (name "unconnected-(U2A-(CLKO{slash}ICP3{slash}INT7)_PE7-Pad9)") (class "Default")
      (node (ref "U2") (pin "9") (pinfunction "(CLKO/ICP3/INT7)_PE7_9") (pintype "bidirectional"))
    )
    (net (code "102") (name "unconnected-(U2A-(ICP1)_PD4-Pad47)") (class "Default")
      (node (ref "U2") (pin "47") (pinfunction "(ICP1)_PD4_47") (pintype "bidirectional"))
    )
    (net (code "103") (name "unconnected-(U2A-(ICP4)_PL0-Pad35)") (class "Default")
      (node (ref "U2") (pin "35") (pinfunction "(ICP4)_PL0_35") (pintype "bidirectional"))
    )
    (net (code "104") (name "unconnected-(U2A-(ICP5)_PL1-Pad36)") (class "Default")
      (node (ref "U2") (pin "36") (pinfunction "(ICP5)_PL1_36") (pintype "bidirectional"))
    )
    (net (code "105") (name "unconnected-(U2A-(OC0A{slash}OC1C{slash}PCINT7)_PB7-Pad26)") (class "Default")
      (node (ref "U2") (pin "26") (pinfunction "(OC0A/OC1C/PCINT7)_PB7_26") (pintype "bidirectional"))
    )
    (net (code "106") (name "unconnected-(U2A-(OC0B)_PG5-Pad1)") (class "Default")
      (node (ref "U2") (pin "1") (pinfunction "(OC0B)_PG5_1") (pintype "bidirectional"))
    )
    (net (code "107") (name "unconnected-(U2A-(OC1A{slash}PCINT5)_PB5-Pad24)") (class "Default")
      (node (ref "U2") (pin "24") (pinfunction "(OC1A/PCINT5)_PB5_24") (pintype "bidirectional"))
    )
    (net (code "108") (name "unconnected-(U2A-(OC1B{slash}PCINT6)_PB6-Pad25)") (class "Default")
      (node (ref "U2") (pin "25") (pinfunction "(OC1B/PCINT6)_PB6_25") (pintype "bidirectional"))
    )
    (net (code "109") (name "unconnected-(U2A-(OC2B)_PH6-Pad18)") (class "Default")
      (node (ref "U2") (pin "18") (pinfunction "(OC2B)_PH6_18") (pintype "bidirectional"))
    )
    (net (code "110") (name "unconnected-(U2A-(OC3A{slash}AIN1)_PE3-Pad5)") (class "Default")
      (node (ref "U2") (pin "5") (pinfunction "(OC3A/AIN1)_PE3_5") (pintype "bidirectional"))
    )
    (net (code "111") (name "unconnected-(U2A-(OC3C{slash}INT5)_PE5-Pad7)") (class "Default")
      (node (ref "U2") (pin "7") (pinfunction "(OC3C/INT5)_PE5_7") (pintype "bidirectional"))
    )
    (net (code "112") (name "unconnected-(U2A-(OC4B)_PH4-Pad16)") (class "Default")
      (node (ref "U2") (pin "16") (pinfunction "(OC4B)_PH4_16") (pintype "bidirectional"))
    )
    (net (code "113") (name "unconnected-(U2A-(OC5A)_PL3-Pad38)") (class "Default")
      (node (ref "U2") (pin "38") (pinfunction "(OC5A)_PL3_38") (pintype "bidirectional"))
    )
    (net (code "114") (name "unconnected-(U2A-(OC5B)_PL4-Pad39)") (class "Default")
      (node (ref "U2") (pin "39") (pinfunction "(OC5B)_PL4_39") (pintype "bidirectional"))
    )
    (net (code "115") (name "unconnected-(U2A-(OC5C)_PL5-Pad40)") (class "Default")
      (node (ref "U2") (pin "40") (pinfunction "(OC5C)_PL5_40") (pintype "bidirectional"))
    )
    (net (code "116") (name "unconnected-(U2A-(T0)_PD7-Pad50)") (class "Default")
      (node (ref "U2") (pin "50") (pinfunction "(T0)_PD7_50") (pintype "bidirectional"))
    )
    (net (code "117") (name "unconnected-(U2A-(T1)_PD6-Pad49)") (class "Default")
      (node (ref "U2") (pin "49") (pinfunction "(T1)_PD6_49") (pintype "bidirectional"))
    )
    (net (code "118") (name "unconnected-(U2A-(T3{slash}INT6)_PE6-Pad8)") (class "Default")
      (node (ref "U2") (pin "8") (pinfunction "(T3/INT6)_PE6_8") (pintype "bidirectional"))
    )
    (net (code "119") (name "unconnected-(U2A-(T4)_PH7-Pad27)") (class "Default")
      (node (ref "U2") (pin "27") (pinfunction "(T4)_PH7_27") (pintype "bidirectional"))
    )
    (net (code "120") (name "unconnected-(U2A-(T5)_PL2-Pad37)") (class "Default")
      (node (ref "U2") (pin "37") (pinfunction "(T5)_PL2_37") (pintype "bidirectional"))
    )
    (net (code "121") (name "unconnected-(U2A-(TOSC1)_PG4-Pad29)") (class "Default")
      (node (ref "U2") (pin "29") (pinfunction "(TOSC1)_PG4_29") (pintype "bidirectional"))
    )
    (net (code "122") (name "unconnected-(U2A-(TOSC2)_PG3-Pad28)") (class "Default")
      (node (ref "U2") (pin "28") (pinfunction "(TOSC2)_PG3_28") (pintype "bidirectional"))
    )
    (net (code "123") (name "unconnected-(U2A-(XCK0{slash}AIN0)_PE2-Pad4)") (class "Default")
      (node (ref "U2") (pin "4") (pinfunction "(XCK0/AIN0)_PE2_4") (pintype "bidirectional"))
    )
    (net (code "124") (name "unconnected-(U2A-(XCK1)_PD5-Pad48)") (class "Default")
      (node (ref "U2") (pin "48") (pinfunction "(XCK1)_PD5_48") (pintype "bidirectional"))
    )
    (net (code "125") (name "unconnected-(U2A-(XCK2)_PH2-Pad14)") (class "Default")
      (node (ref "U2") (pin "14") (pinfunction "(XCK2)_PH2_14") (pintype "bidirectional"))
    )
    (net (code "126") (name "unconnected-(U2A-(~{SS}{slash}PCINT0)_PB0-Pad19)") (class "Default")
      (node (ref "U2") (pin "19") (pinfunction "(~{SS}/PCINT0)_PB0_19") (pintype "bidirectional"))
    )
    (net (code "127") (name "unconnected-(U2A-PL6-Pad41)") (class "Default")
      (node (ref "U2") (pin "41") (pinfunction "PL6_41") (pintype "bidirectional"))
    )
    (net (code "128") (name "unconnected-(U2A-PL7-Pad42)") (class "Default")
      (node (ref "U2") (pin "42") (pinfunction "PL7_42") (pintype "bidirectional"))
    )
    (net (code "129") (name "unconnected-(U2B-(PCINT12)PJ3-Pad66)") (class "Default")
      (node (ref "U2") (pin "66") (pinfunction "(PCINT12)PJ3_66") (pintype "bidirectional"))
    )
    (net (code "130") (name "unconnected-(U2B-(XCK3{slash}PCINT11)PJ2-Pad65)") (class "Default")
      (node (ref "U2") (pin "65") (pinfunction "(XCK3/PCINT11)PJ2_65") (pintype "bidirectional"))
    )
    (net (code "131") (name "unconnected-(U2B-PA0_(AD0)-Pad78)") (class "Default")
      (node (ref "U2") (pin "78") (pinfunction "PA0_(AD0)_78") (pintype "bidirectional"))
    )
    (net (code "132") (name "unconnected-(U2B-PA1_(AD1)-Pad77)") (class "Default")
      (node (ref "U2") (pin "77") (pinfunction "PA1_(AD1)_77") (pintype "bidirectional"))
    )
    (net (code "133") (name "unconnected-(U2B-PA2_(AD2)-Pad76)") (class "Default")
      (node (ref "U2") (pin "76") (pinfunction "PA2_(AD2)_76") (pintype "bidirectional"))
    )
    (net (code "134") (name "unconnected-(U2B-PA3_(AD3)-Pad75)") (class "Default")
      (node (ref "U2") (pin "75") (pinfunction "PA3_(AD3)_75") (pintype "bidirectional"))
    )
    (net (code "135") (name "unconnected-(U2B-PA4_(AD4)-Pad74)") (class "Default")
      (node (ref "U2") (pin "74") (pinfunction "PA4_(AD4)_74") (pintype "bidirectional"))
    )
    (net (code "136") (name "unconnected-(U2B-PA5_(AD5)-Pad73)") (class "Default")
      (node (ref "U2") (pin "73") (pinfunction "PA5_(AD5)_73") (pintype "bidirectional"))
    )
    (net (code "137") (name "unconnected-(U2B-PA6_(AD6)-Pad72)") (class "Default")
      (node (ref "U2") (pin "72") (pinfunction "PA6_(AD6)_72") (pintype "bidirectional"))
    )
    (net (code "138") (name "unconnected-(U2B-PA7_(AD7)-Pad71)") (class "Default")
      (node (ref "U2") (pin "71") (pinfunction "PA7_(AD7)_71") (pintype "bidirectional"))
    )
    (net (code "139") (name "unconnected-(U2B-PC0(A8)-Pad53)") (class "Default")
      (node (ref "U2") (pin "53") (pinfunction "PC0(A8)_53") (pintype "bidirectional"))
    )
    (net (code "140") (name "unconnected-(U2B-PC1(A9)-Pad54)") (class "Default")
      (node (ref "U2") (pin "54") (pinfunction "PC1(A9)_54") (pintype "bidirectional"))
    )
    (net (code "141") (name "unconnected-(U2B-PC2(A10)-Pad55)") (class "Default")
      (node (ref "U2") (pin "55") (pinfunction "PC2(A10)_55") (pintype "bidirectional"))
    )
    (net (code "142") (name "unconnected-(U2B-PC3(A11)-Pad56)") (class "Default")
      (node (ref "U2") (pin "56") (pinfunction "PC3(A11)_56") (pintype "bidirectional"))
    )
    (net (code "143") (name "unconnected-(U2B-PC4(A12)-Pad57)") (class "Default")
      (node (ref "U2") (pin "57") (pinfunction "PC4(A12)_57") (pintype "bidirectional"))
    )
    (net (code "144") (name "unconnected-(U2B-PC7(A15)-Pad60)") (class "Default")
      (node (ref "U2") (pin "60") (pinfunction "PC7(A15)_60") (pintype "bidirectional"))
    )
    (net (code "145") (name "unconnected-(U2B-PF0_(ADC0)-Pad97)") (class "Default")
      (node (ref "U2") (pin "97") (pinfunction "PF0_(ADC0)_97") (pintype "bidirectional"))
    )
    (net (code "146") (name "unconnected-(U2B-PF1_(ADC1)-Pad96)") (class "Default")
      (node (ref "U2") (pin "96") (pinfunction "PF1_(ADC1)_96") (pintype "bidirectional"))
    )
    (net (code "147") (name "unconnected-(U2B-PF2_(ADC2)-Pad95)") (class "Default")
      (node (ref "U2") (pin "95") (pinfunction "PF2_(ADC2)_95") (pintype "bidirectional"))
    )
    (net (code "148") (name "unconnected-(U2B-PF3_(ADC3)-Pad94)") (class "Default")
      (node (ref "U2") (pin "94") (pinfunction "PF3_(ADC3)_94") (pintype "bidirectional"))
    )
    (net (code "149") (name "unconnected-(U2B-PF4_(ADC4{slash}TCK)-Pad93)") (class "Default")
      (node (ref "U2") (pin "93") (pinfunction "PF4_(ADC4/TCK)_93") (pintype "bidirectional"))
    )
    (net (code "150") (name "unconnected-(U2B-PF5_(ADC5{slash}TMS)-Pad92)") (class "Default")
      (node (ref "U2") (pin "92") (pinfunction "PF5_(ADC5/TMS)_92") (pintype "bidirectional"))
    )
    (net (code "151") (name "unconnected-(U2B-PF6_(ADC6{slash}TDO)-Pad91)") (class "Default")
      (node (ref "U2") (pin "91") (pinfunction "PF6_(ADC6/TDO)_91") (pintype "bidirectional"))
    )
    (net (code "152") (name "unconnected-(U2B-PF7_(ADC7{slash}TDI)-Pad90)") (class "Default")
      (node (ref "U2") (pin "90") (pinfunction "PF7_(ADC7/TDI)_90") (pintype "bidirectional"))
    )
    (net (code "153") (name "unconnected-(U2B-PG0(~{WR})-Pad51)") (class "Default")
      (node (ref "U2") (pin "51") (pinfunction "PG0(~{WR})_51") (pintype "bidirectional"))
    )
    (net (code "154") (name "unconnected-(U2B-PG1(~{RD})-Pad52)") (class "Default")
      (node (ref "U2") (pin "52") (pinfunction "PG1(~{RD})_52") (pintype "bidirectional"))
    )
    (net (code "155") (name "unconnected-(U2B-PG2_(ALE)-Pad70)") (class "Default")
      (node (ref "U2") (pin "70") (pinfunction "PG2_(ALE)_70") (pintype "bidirectional"))
    )
    (net (code "156") (name "unconnected-(U2B-PJ4_(PCINT13)-Pad67)") (class "Default")
      (node (ref "U2") (pin "67") (pinfunction "PJ4_(PCINT13)_67") (pintype "bidirectional"))
    )
    (net (code "157") (name "unconnected-(U2B-PJ5_(PCINT14)-Pad68)") (class "Default")
      (node (ref "U2") (pin "68") (pinfunction "PJ5_(PCINT14)_68") (pintype "bidirectional"))
    )
    (net (code "158") (name "unconnected-(U2B-PJ6_(PCINT15)-Pad69)") (class "Default")
      (node (ref "U2") (pin "69") (pinfunction "PJ6_(PCINT15)_69") (pintype "bidirectional"))
    )
    (net (code "159") (name "unconnected-(U2B-PJ7-Pad79)") (class "Default")
      (node (ref "U2") (pin "79") (pinfunction "PJ7_79") (pintype "bidirectional"))
    )
    (net (code "160") (name "unconnected-(U2B-PK0_(ADC8{slash}PCINT16)-Pad89)") (class "Default")
      (node (ref "U2") (pin "89") (pinfunction "PK0_(ADC8/PCINT16)_89") (pintype "bidirectional"))
    )
    (net (code "161") (name "unconnected-(U2B-PK1_(ADC9{slash}PCINT17)-Pad88)") (class "Default")
      (node (ref "U2") (pin "88") (pinfunction "PK1_(ADC9/PCINT17)_88") (pintype "bidirectional"))
    )
    (net (code "162") (name "unconnected-(U2B-PK2_(ADC10{slash}PCINT18)-Pad87)") (class "Default")
      (node (ref "U2") (pin "87") (pinfunction "PK2_(ADC10/PCINT18)_87") (pintype "bidirectional"))
    )
    (net (code "163") (name "unconnected-(U2B-PK3_(ADC11{slash}PCINT19)-Pad86)") (class "Default")
      (node (ref "U2") (pin "86") (pinfunction "PK3_(ADC11/PCINT19)_86") (pintype "bidirectional"))
    )
    (net (code "164") (name "unconnected-(U2B-PK4_(ADC12{slash}PCINT20)-Pad85)") (class "Default")
      (node (ref "U2") (pin "85") (pinfunction "PK4_(ADC12/PCINT20)_85") (pintype "bidirectional"))
    )
    (net (code "165") (name "unconnected-(U2B-PK5_(ADC13{slash}PCINT21)-Pad84)") (class "Default")
      (node (ref "U2") (pin "84") (pinfunction "PK5_(ADC13/PCINT21)_84") (pintype "bidirectional"))
    )
    (net (code "166") (name "unconnected-(U2B-PK6_(ADC14{slash}PCINT22)-Pad83)") (class "Default")
      (node (ref "U2") (pin "83") (pinfunction "PK6_(ADC14/PCINT22)_83") (pintype "bidirectional"))
    )
    (net (code "167") (name "unconnected-(U2B-PK7_(ADC15{slash}PCINT23)-Pad82)") (class "Default")
      (node (ref "U2") (pin "82") (pinfunction "PK7_(ADC15/PCINT23)_82") (pintype "bidirectional"))
    )
    (net (code "168") (name "unconnected-(U4-CBUS0-Pad18)") (class "Default")
      (node (ref "U4") (pin "18") (pinfunction "CBUS0_18") (pintype "bidirectional"))
    )
    (net (code "169") (name "unconnected-(U4-CBUS1-Pad17)") (class "Default")
      (node (ref "U4") (pin "17") (pinfunction "CBUS1_17") (pintype "bidirectional"))
    )
    (net (code "170") (name "unconnected-(U4-CBUS2-Pad10)") (class "Default")
      (node (ref "U4") (pin "10") (pinfunction "CBUS2_10") (pintype "bidirectional"))
    )
    (net (code "171") (name "unconnected-(U4-CBUS3-Pad19)") (class "Default")
      (node (ref "U4") (pin "19") (pinfunction "CBUS3_19") (pintype "bidirectional"))
    )
    (net (code "172") (name "unconnected-(U4-~{CTS}-Pad9)") (class "Default")
      (node (ref "U4") (pin "9") (pinfunction "~{CTS}_9") (pintype "bidirectional"))
    )
    (net (code "173") (name "unconnected-(U4-~{DCD}-Pad8)") (class "Default")
      (node (ref "U4") (pin "8") (pinfunction "~{DCD}_8") (pintype "bidirectional"))
    )
    (net (code "174") (name "unconnected-(U4-~{DSR}-Pad7)") (class "Default")
      (node (ref "U4") (pin "7") (pinfunction "~{DSR}_7") (pintype "bidirectional"))
    )
    (net (code "175") (name "unconnected-(U4-~{RESET}-Pad14)") (class "Default")
      (node (ref "U4") (pin "14") (pinfunction "~{RESET}_14") (pintype "bidirectional"))
    )
    (net (code "176") (name "unconnected-(U4-~{RI}-Pad5)") (class "Default")
      (node (ref "U4") (pin "5") (pinfunction "~{RI}_5") (pintype "bidirectional"))
    )
    (net (code "177") (name "unconnected-(U4-~{RTS}-Pad2)") (class "Default")
      (node (ref "U4") (pin "2") (pinfunction "~{RTS}_2") (pintype "bidirectional"))
    )
    (net (code "178") (name "unconnected-(XBEE-900HP-AD0{slash}DIO0-Pad20)") (class "Default")
      (node (ref "XBEE-900HP") (pin "20") (pinfunction "AD0/DIO0_20") (pintype "bidirectional"))
    )
    (net (code "179") (name "unconnected-(XBEE-900HP-AD1{slash}DIO1-Pad19)") (class "Default")
      (node (ref "XBEE-900HP") (pin "19") (pinfunction "AD1/DIO1_19") (pintype "bidirectional"))
    )
    (net (code "180") (name "unconnected-(XBEE-900HP-AD2{slash}DIO2-Pad18)") (class "Default")
      (node (ref "XBEE-900HP") (pin "18") (pinfunction "AD2/DIO2_18") (pintype "bidirectional"))
    )
    (net (code "181") (name "unconnected-(XBEE-900HP-AD3{slash}DIO3-Pad17)") (class "Default")
      (node (ref "XBEE-900HP") (pin "17") (pinfunction "AD3/DIO3_17") (pintype "bidirectional"))
    )
    (net (code "182") (name "unconnected-(XBEE-900HP-AD4{slash}DIO4-Pad11)") (class "Default")
      (node (ref "XBEE-900HP") (pin "11") (pinfunction "AD4/DIO4_11") (pintype "bidirectional"))
    )
    (net (code "183") (name "unconnected-(XBEE-900HP-ASC{slash}AD5{slash}DIO5-Pad15)") (class "Default")
      (node (ref "XBEE-900HP") (pin "15") (pinfunction "ASC/AD5/DIO5_15") (pintype "bidirectional"))
    )
    (net (code "184") (name "unconnected-(XBEE-900HP-DO8-Pad4)") (class "Default")
      (node (ref "XBEE-900HP") (pin "4") (pinfunction "DO8_4") (pintype "output"))
    )
    (net (code "185") (name "unconnected-(XBEE-900HP-DTR{slash}DI8-Pad9)") (class "Default")
      (node (ref "XBEE-900HP") (pin "9") (pinfunction "DTR/DI8_9") (pintype "input"))
    )
    (net (code "186") (name "unconnected-(XBEE-900HP-PWM0{slash}RSSI-Pad6)") (class "Default")
      (node (ref "XBEE-900HP") (pin "6") (pinfunction "PWM0/RSSI_6") (pintype "output"))
    )
    (net (code "187") (name "unconnected-(XBEE-900HP-PWM1-Pad7)") (class "Default")
      (node (ref "XBEE-900HP") (pin "7") (pinfunction "PWM1_7") (pintype "output"))
    )
    (net (code "188") (name "unconnected-(XBEE-900HP-RESERVED-Pad8)") (class "Default")
      (node (ref "XBEE-900HP") (pin "8") (pinfunction "RESERVED_8") (pintype "no_connect"))
    )
  )
)
